# arduino.net
KiCad netlist of a schematic drawn in EAGLE
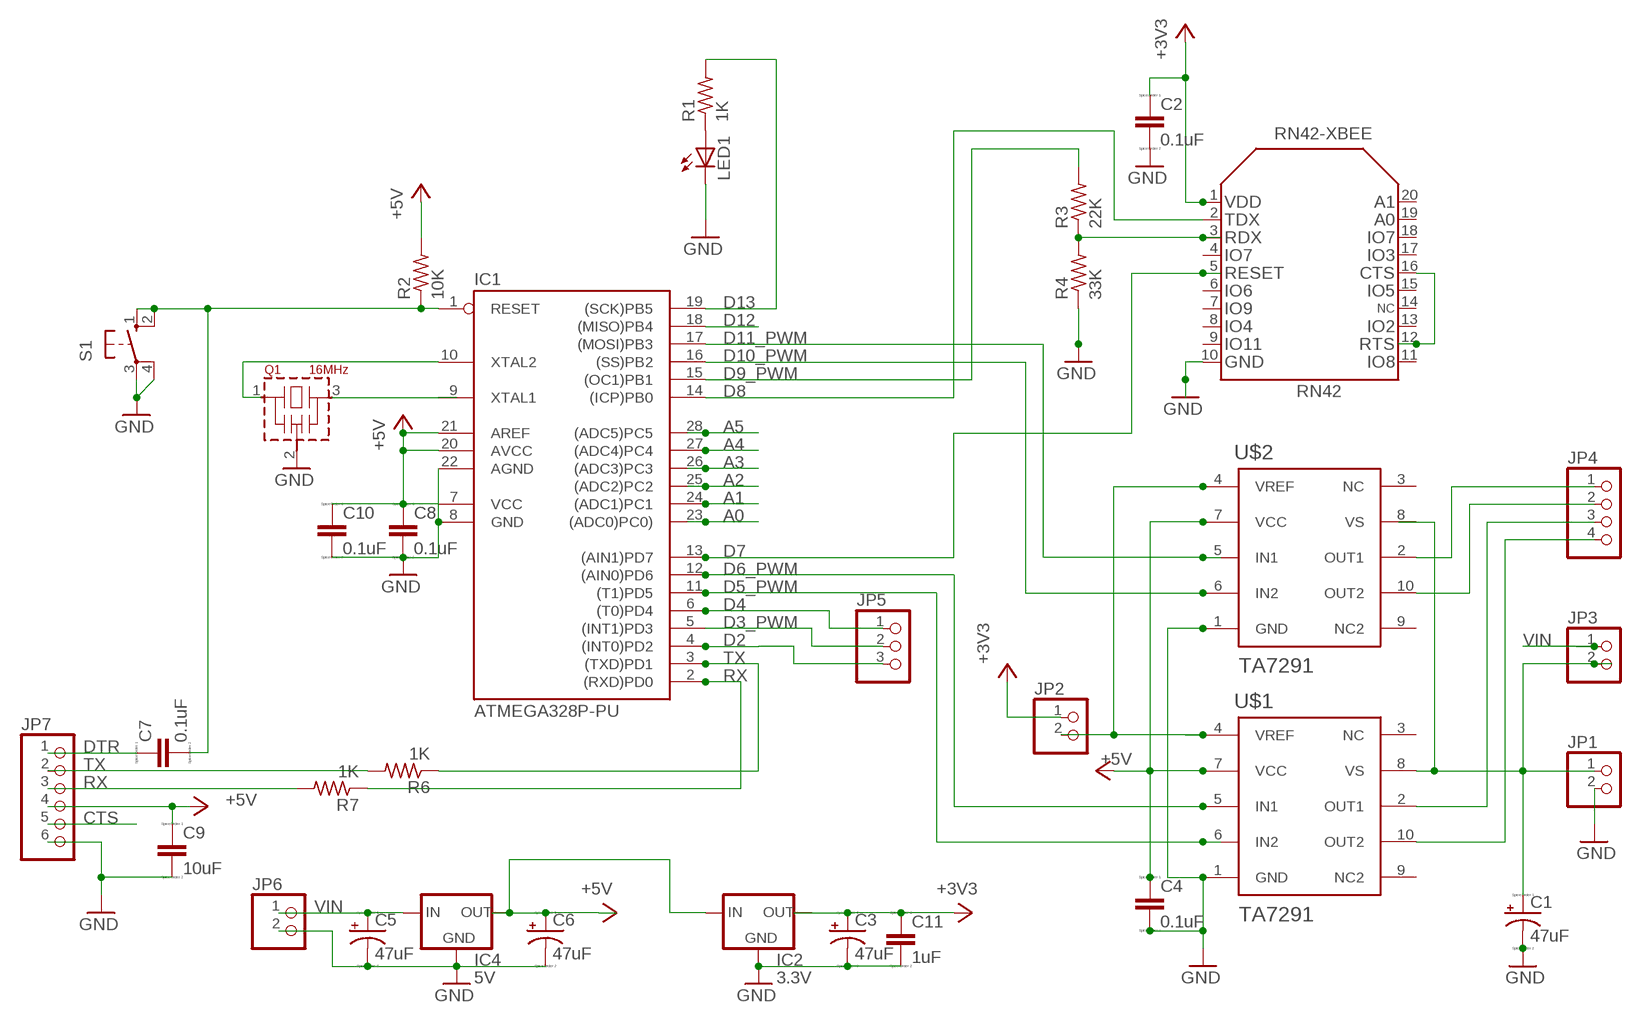
[diagram p0: schematic, sheet 1]

(export (version "E")
  (design (tool "Eeschema 10.0.6"))
  (components
    (comp (ref "C1")
      (value "47uF")
      (footprint "eagle-import:E2-5")
      (libsource (lib "eagle-import") (part "CPOL-USE2-5"))
    )
    (comp (ref "C2")
      (value "0.1uF")
      (footprint "eagle-import:C050-025X075")
      (libsource (lib "eagle-import") (part "C-EU050-025X075"))
    )
    (comp (ref "C3")
      (value "47uF")
      (footprint "eagle-import:E2-5")
      (libsource (lib "eagle-import") (part "CPOL-USE2-5"))
    )
    (comp (ref "C4")
      (value "0.1uF")
      (footprint "eagle-import:C050-025X075")
      (libsource (lib "eagle-import") (part "C-EU050-025X075"))
    )
    (comp (ref "C5")
      (value "47uF")
      (footprint "eagle-import:E2-5")
      (libsource (lib "eagle-import") (part "CPOL-USE2-5"))
    )
    (comp (ref "C6")
      (value "47uF")
      (footprint "eagle-import:E2-5")
      (libsource (lib "eagle-import") (part "CPOL-USE2-5"))
    )
    (comp (ref "C7")
      (value "0.1uF")
      (footprint "eagle-import:C050-025X075")
      (libsource (lib "eagle-import") (part "C-EU050-025X075"))
    )
    (comp (ref "C8")
      (value "0.1uF")
      (footprint "eagle-import:C050-025X075")
      (libsource (lib "eagle-import") (part "C-EU050-025X075"))
    )
    (comp (ref "C9")
      (value "10uF")
      (footprint "eagle-import:C050-025X075")
      (libsource (lib "eagle-import") (part "C-EU050-025X075"))
    )
    (comp (ref "C10")
      (value "0.1uF")
      (footprint "eagle-import:C050-025X075")
      (libsource (lib "eagle-import") (part "C-EU050-025X075"))
    )
    (comp (ref "C11")
      (value "1uF")
      (footprint "eagle-import:C050-025X075")
      (libsource (lib "eagle-import") (part "C-EU050-025X075"))
    )
    (comp (ref "IC1")
      (value "ATMEGA328P-PU")
      (footprint "eagle-import:DIL28-3")
      (libsource (lib "eagle-import") (part "ATMEGA328P-PU"))
    )
    (comp (ref "IC2")
      (value "3.3V")
      (footprint "eagle-import:78XXS")
      (libsource (lib "eagle-import") (part "78XXS"))
    )
    (comp (ref "IC4")
      (value "5V")
      (footprint "eagle-import:78XXS")
      (libsource (lib "eagle-import") (part "78XXS"))
    )
    (comp (ref "JP1")
      (value "PINHD-1X2")
      (footprint "eagle-import:1X02")
      (libsource (lib "eagle-import") (part "PINHD-1X2"))
    )
    (comp (ref "JP2")
      (value "PINHD-1X2")
      (footprint "eagle-import:1X02")
      (libsource (lib "eagle-import") (part "PINHD-1X2"))
    )
    (comp (ref "JP3")
      (value "PINHD-1X2")
      (footprint "eagle-import:1X02")
      (libsource (lib "eagle-import") (part "PINHD-1X2"))
    )
    (comp (ref "JP4")
      (value "PINHD-1X4")
      (footprint "eagle-import:1X04")
      (libsource (lib "eagle-import") (part "PINHD-1X4"))
    )
    (comp (ref "JP5")
      (value "PINHD-1X3")
      (footprint "eagle-import:1X03")
      (libsource (lib "eagle-import") (part "PINHD-1X3"))
    )
    (comp (ref "JP6")
      (value "PINHD-1X2")
      (footprint "eagle-import:1X02")
      (libsource (lib "eagle-import") (part "PINHD-1X2"))
    )
    (comp (ref "JP7")
      (value "PINHD-1X6")
      (footprint "eagle-import:1X06")
      (libsource (lib "eagle-import") (part "PINHD-1X6"))
    )
    (comp (ref "LED1")
      (value "LED3MM")
      (footprint "eagle-import:LED3MM")
      (libsource (lib "eagle-import") (part "LED3MM"))
    )
    (comp (ref "Q1")
      (value "16MHz")
      (footprint "eagle-import:CSTLS_G9")
      (libsource (lib "eagle-import") (part "murata-resonators_CSTLS_G"))
    )
    (comp (ref "R1")
      (value "1K")
      (footprint "eagle-import:0207_10")
      (libsource (lib "eagle-import") (part "R-US_0207/10"))
    )
    (comp (ref "R2")
      (value "10K")
      (footprint "eagle-import:0207_10")
      (libsource (lib "eagle-import") (part "R-US_0207/10"))
    )
    (comp (ref "R3")
      (value "22K")
      (footprint "eagle-import:0207_10")
      (libsource (lib "eagle-import") (part "R-US_0207/10"))
    )
    (comp (ref "R4")
      (value "33K")
      (footprint "eagle-import:0207_10")
      (libsource (lib "eagle-import") (part "R-US_0207/10"))
    )
    (comp (ref "R6")
      (value "1K")
      (footprint "eagle-import:0207_10")
      (libsource (lib "eagle-import") (part "R-US_0207/10"))
    )
    (comp (ref "R7")
      (value "1K")
      (footprint "eagle-import:0207_10")
      (libsource (lib "eagle-import") (part "R-US_0207/10"))
    )
    (comp (ref "S1")
      (value "10-XX")
      (footprint "eagle-import:B3F-10XX")
      (fields (field (name "MPN") "B3F-1000"))
      (libsource (lib "eagle-import") (part "10-XX"))
    )
    (comp (ref "U$1")
      (value "TA7291")
      (footprint "eagle-import:HSIP10")
      (libsource (lib "eagle-import") (part "TA7291"))
    )
    (comp (ref "U$2")
      (value "TA7291")
      (footprint "eagle-import:HSIP10")
      (libsource (lib "eagle-import") (part "TA7291"))
    )
    (comp (ref "U$3")
      (value "RN42-XBEE")
      (footprint "eagle-import:RN42-XBEE-PKG")
      (libsource (lib "eagle-import") (part "RN42-XBEE"))
    )
  )
  (nets
    (net (code "1") (name "+3V3") (class "Default")
      (node (ref "C11") (pin "1") (pinfunction "1_1") (pintype "passive"))
      (node (ref "C2") (pin "1") (pinfunction "1_1") (pintype "passive"))
      (node (ref "C3") (pin "+") (pinfunction "+_+") (pintype "passive"))
      (node (ref "IC2") (pin "OUT") (pinfunction "OUT_OUT") (pintype "passive"))
      (node (ref "JP2") (pin "1") (pinfunction "1_1") (pintype "passive"))
      (node (ref "U$3") (pin "1") (pinfunction "1_1") (pintype "passive"))
    )
    (net (code "2") (name "+5V") (class "Default")
      (node (ref "C10") (pin "1") (pinfunction "1_1") (pintype "passive"))
      (node (ref "C4") (pin "1") (pinfunction "1_1") (pintype "passive"))
      (node (ref "C6") (pin "+") (pinfunction "+_+") (pintype "passive"))
      (node (ref "C8") (pin "1") (pinfunction "1_1") (pintype "passive"))
      (node (ref "C9") (pin "1") (pinfunction "1_1") (pintype "passive"))
      (node (ref "IC1") (pin "20") (pinfunction "AVCC_20") (pintype "power_in"))
      (node (ref "IC1") (pin "21") (pinfunction "AREF_21") (pintype "passive"))
      (node (ref "IC1") (pin "7") (pinfunction "VCC_7") (pintype "power_in"))
      (node (ref "IC2") (pin "IN") (pinfunction "IN_IN") (pintype "input"))
      (node (ref "IC4") (pin "OUT") (pinfunction "OUT_OUT") (pintype "passive"))
      (node (ref "JP7") (pin "4") (pinfunction "4_4") (pintype "passive"))
      (node (ref "R2") (pin "2") (pinfunction "2_2") (pintype "passive"))
      (node (ref "U$1") (pin "7") (pinfunction "VCC_7") (pintype "bidirectional"))
      (node (ref "U$2") (pin "7") (pinfunction "VCC_7") (pintype "bidirectional"))
    )
    (net (code "3") (name "/A0") (class "Default")
      (node (ref "IC1") (pin "23") (pinfunction "(ADC0)PC0)_23") (pintype "bidirectional"))
    )
    (net (code "4") (name "/A1") (class "Default")
      (node (ref "IC1") (pin "24") (pinfunction "(ADC1)PC1_24") (pintype "bidirectional"))
    )
    (net (code "5") (name "/A2") (class "Default")
      (node (ref "IC1") (pin "25") (pinfunction "(ADC2)PC2_25") (pintype "bidirectional"))
    )
    (net (code "6") (name "/A3") (class "Default")
      (node (ref "IC1") (pin "26") (pinfunction "(ADC3)PC3_26") (pintype "bidirectional"))
    )
    (net (code "7") (name "/A4") (class "Default")
      (node (ref "IC1") (pin "27") (pinfunction "(ADC4)PC4_27") (pintype "bidirectional"))
    )
    (net (code "8") (name "/A5") (class "Default")
      (node (ref "IC1") (pin "28") (pinfunction "(ADC5)PC5_28") (pintype "bidirectional"))
    )
    (net (code "9") (name "/CTS") (class "Default")
      (node (ref "JP7") (pin "5") (pinfunction "5_5") (pintype "passive"))
    )
    (net (code "10") (name "/D2") (class "Default")
      (node (ref "IC1") (pin "4") (pinfunction "(INT0)PD2_4") (pintype "bidirectional"))
      (node (ref "JP5") (pin "3") (pinfunction "3_3") (pintype "passive"))
    )
    (net (code "11") (name "/D3_PWM") (class "Default")
      (node (ref "IC1") (pin "5") (pinfunction "(INT1)PD3_5") (pintype "bidirectional"))
      (node (ref "JP5") (pin "2") (pinfunction "2_2") (pintype "passive"))
    )
    (net (code "12") (name "/D4") (class "Default")
      (node (ref "IC1") (pin "6") (pinfunction "(T0)PD4_6") (pintype "bidirectional"))
      (node (ref "JP5") (pin "1") (pinfunction "1_1") (pintype "passive"))
    )
    (net (code "13") (name "/D5_PWM") (class "Default")
      (node (ref "IC1") (pin "11") (pinfunction "(T1)PD5_11") (pintype "bidirectional"))
      (node (ref "U$1") (pin "6") (pinfunction "IN2_6") (pintype "bidirectional"))
    )
    (net (code "14") (name "/D6_PWM") (class "Default")
      (node (ref "IC1") (pin "12") (pinfunction "(AIN0)PD6_12") (pintype "bidirectional"))
      (node (ref "U$1") (pin "5") (pinfunction "IN1_5") (pintype "bidirectional"))
    )
    (net (code "15") (name "/D7") (class "Default")
      (node (ref "IC1") (pin "13") (pinfunction "(AIN1)PD7_13") (pintype "bidirectional"))
      (node (ref "U$3") (pin "5") (pinfunction "5_5") (pintype "passive"))
    )
    (net (code "16") (name "/D8") (class "Default")
      (node (ref "IC1") (pin "14") (pinfunction "(ICP)PB0_14") (pintype "bidirectional"))
      (node (ref "U$3") (pin "2") (pinfunction "2_2") (pintype "passive"))
    )
    (net (code "17") (name "/D9_PWM") (class "Default")
      (node (ref "IC1") (pin "15") (pinfunction "(OC1)PB1_15") (pintype "bidirectional"))
      (node (ref "R3") (pin "2") (pinfunction "2_2") (pintype "passive"))
    )
    (net (code "18") (name "/D10_PWM") (class "Default")
      (node (ref "IC1") (pin "16") (pinfunction "(SS)PB2_16") (pintype "bidirectional"))
      (node (ref "U$2") (pin "6") (pinfunction "IN2_6") (pintype "bidirectional"))
    )
    (net (code "19") (name "/D11_PWM") (class "Default")
      (node (ref "IC1") (pin "17") (pinfunction "(MOSI)PB3_17") (pintype "bidirectional"))
      (node (ref "U$2") (pin "5") (pinfunction "IN1_5") (pintype "bidirectional"))
    )
    (net (code "20") (name "/D12") (class "Default")
      (node (ref "IC1") (pin "18") (pinfunction "(MISO)PB4_18") (pintype "bidirectional"))
    )
    (net (code "21") (name "/D13") (class "Default")
      (node (ref "IC1") (pin "19") (pinfunction "(SCK)PB5_19") (pintype "bidirectional"))
      (node (ref "R1") (pin "2") (pinfunction "2_2") (pintype "passive"))
    )
    (net (code "22") (name "/DTR") (class "Default")
      (node (ref "C7") (pin "1") (pinfunction "1_1") (pintype "passive"))
      (node (ref "JP7") (pin "1") (pinfunction "1_1") (pintype "passive"))
    )
    (net (code "23") (name "/RX") (class "Default")
      (node (ref "IC1") (pin "2") (pinfunction "(RXD)PD0_2") (pintype "bidirectional"))
      (node (ref "R7") (pin "1") (pinfunction "1_1") (pintype "passive"))
    )
    (net (code "24") (name "/TX") (class "Default")
      (node (ref "IC1") (pin "3") (pinfunction "(TXD)PD1_3") (pintype "bidirectional"))
      (node (ref "R6") (pin "1") (pinfunction "1_1") (pintype "passive"))
    )
    (net (code "25") (name "/VIN") (class "Default")
      (node (ref "C5") (pin "+") (pinfunction "+_+") (pintype "passive"))
      (node (ref "IC4") (pin "IN") (pinfunction "IN_IN") (pintype "input"))
      (node (ref "JP3") (pin "1") (pinfunction "1_1") (pintype "passive"))
      (node (ref "JP6") (pin "1") (pinfunction "1_1") (pintype "passive"))
    )
    (net (code "26") (name "GND") (class "Default")
      (node (ref "C1") (pin "-") (pinfunction "-_-") (pintype "passive"))
      (node (ref "C10") (pin "2") (pinfunction "2_2") (pintype "passive"))
      (node (ref "C11") (pin "2") (pinfunction "2_2") (pintype "passive"))
      (node (ref "C2") (pin "2") (pinfunction "2_2") (pintype "passive"))
      (node (ref "C3") (pin "-") (pinfunction "-_-") (pintype "passive"))
      (node (ref "C4") (pin "2") (pinfunction "2_2") (pintype "passive"))
      (node (ref "C5") (pin "-") (pinfunction "-_-") (pintype "passive"))
      (node (ref "C6") (pin "-") (pinfunction "-_-") (pintype "passive"))
      (node (ref "C8") (pin "2") (pinfunction "2_2") (pintype "passive"))
      (node (ref "C9") (pin "2") (pinfunction "2_2") (pintype "passive"))
      (node (ref "IC1") (pin "22") (pinfunction "AGND_22") (pintype "power_in"))
      (node (ref "IC1") (pin "8") (pinfunction "GND_8") (pintype "power_in"))
      (node (ref "IC2") (pin "GND") (pinfunction "GND_GND") (pintype "input"))
      (node (ref "IC4") (pin "GND") (pinfunction "GND_GND") (pintype "input"))
      (node (ref "JP1") (pin "2") (pinfunction "2_2") (pintype "passive"))
      (node (ref "JP6") (pin "2") (pinfunction "2_2") (pintype "passive"))
      (node (ref "JP7") (pin "6") (pinfunction "6_6") (pintype "passive"))
      (node (ref "LED1") (pin "K") (pinfunction "C_K") (pintype "passive"))
      (node (ref "Q1") (pin "2") (pinfunction "VSS_2") (pintype "power_in"))
      (node (ref "R4") (pin "1") (pinfunction "1_1") (pintype "passive"))
      (node (ref "S1") (pin "3") (pinfunction "P_3") (pintype "passive"))
      (node (ref "S1") (pin "4") (pinfunction "P1_4") (pintype "passive"))
      (node (ref "U$1") (pin "1") (pinfunction "GND_1") (pintype "bidirectional"))
      (node (ref "U$2") (pin "1") (pinfunction "GND_1") (pintype "bidirectional"))
      (node (ref "U$3") (pin "10") (pinfunction "10_10") (pintype "passive"))
    )
    (net (code "27") (name "Net-(IC1-RESET)") (class "Default")
      (node (ref "C7") (pin "2") (pinfunction "2_2") (pintype "passive"))
      (node (ref "IC1") (pin "1") (pinfunction "RESET_1") (pintype "input"))
      (node (ref "R2") (pin "1") (pinfunction "1_1") (pintype "passive"))
      (node (ref "S1") (pin "1") (pinfunction "S_1") (pintype "passive"))
      (node (ref "S1") (pin "2") (pinfunction "S1_2") (pintype "passive"))
    )
    (net (code "28") (name "Net-(IC1-XTAL1)") (class "Default")
      (node (ref "IC1") (pin "9") (pinfunction "XTAL1_9") (pintype "bidirectional"))
      (node (ref "Q1") (pin "3") (pinfunction "3_3") (pintype "input"))
    )
    (net (code "29") (name "Net-(IC1-XTAL2)") (class "Default")
      (node (ref "IC1") (pin "10") (pinfunction "XTAL2_10") (pintype "bidirectional"))
      (node (ref "Q1") (pin "1") (pinfunction "1_1") (pintype "output"))
    )
    (net (code "30") (name "Net-(JP7-Pad2)") (class "Default")
      (node (ref "JP7") (pin "2") (pinfunction "2_2") (pintype "passive"))
      (node (ref "R6") (pin "2") (pinfunction "2_2") (pintype "passive"))
    )
    (net (code "31") (name "Net-(JP7-Pad3)") (class "Default")
      (node (ref "JP7") (pin "3") (pinfunction "3_3") (pintype "passive"))
      (node (ref "R7") (pin "2") (pinfunction "2_2") (pintype "passive"))
    )
    (net (code "32") (name "Net-(LED1-PadA)") (class "Default")
      (node (ref "LED1") (pin "A") (pinfunction "A_A") (pintype "passive"))
      (node (ref "R1") (pin "1") (pinfunction "1_1") (pintype "passive"))
    )
    (net (code "33") (name "Net-(R3-Pad1)") (class "Default")
      (node (ref "R3") (pin "1") (pinfunction "1_1") (pintype "passive"))
      (node (ref "R4") (pin "2") (pinfunction "2_2") (pintype "passive"))
      (node (ref "U$3") (pin "3") (pinfunction "3_3") (pintype "passive"))
    )
    (net (code "34") (name "Net-(U$1-OUT1)") (class "Default")
      (node (ref "JP4") (pin "3") (pinfunction "3_3") (pintype "passive"))
      (node (ref "U$1") (pin "2") (pinfunction "OUT1_2") (pintype "bidirectional"))
    )
    (net (code "35") (name "Net-(U$1-OUT2)") (class "Default")
      (node (ref "JP4") (pin "4") (pinfunction "4_4") (pintype "passive"))
      (node (ref "U$1") (pin "10") (pinfunction "OUT2_10") (pintype "bidirectional"))
    )
    (net (code "36") (name "Net-(U$1-VREF)") (class "Default")
      (node (ref "JP2") (pin "2") (pinfunction "2_2") (pintype "passive"))
      (node (ref "U$1") (pin "4") (pinfunction "VREF_4") (pintype "bidirectional"))
      (node (ref "U$2") (pin "4") (pinfunction "VREF_4") (pintype "bidirectional"))
    )
    (net (code "37") (name "Net-(U$1-VS)") (class "Default")
      (node (ref "C1") (pin "+") (pinfunction "+_+") (pintype "passive"))
      (node (ref "JP1") (pin "1") (pinfunction "1_1") (pintype "passive"))
      (node (ref "JP3") (pin "2") (pinfunction "2_2") (pintype "passive"))
      (node (ref "U$1") (pin "8") (pinfunction "VS_8") (pintype "bidirectional"))
      (node (ref "U$2") (pin "8") (pinfunction "VS_8") (pintype "bidirectional"))
    )
    (net (code "38") (name "Net-(U$2-OUT1)") (class "Default")
      (node (ref "JP4") (pin "1") (pinfunction "1_1") (pintype "passive"))
      (node (ref "U$2") (pin "2") (pinfunction "OUT1_2") (pintype "bidirectional"))
    )
    (net (code "39") (name "Net-(U$2-OUT2)") (class "Default")
      (node (ref "JP4") (pin "2") (pinfunction "2_2") (pintype "passive"))
      (node (ref "U$2") (pin "10") (pinfunction "OUT2_10") (pintype "bidirectional"))
    )
    (net (code "40") (name "Net-(U$3-Pad12)") (class "Default")
      (node (ref "U$3") (pin "12") (pinfunction "12_12") (pintype "passive"))
      (node (ref "U$3") (pin "16") (pinfunction "16_16") (pintype "passive"))
    )
    (net (code "41") (name "unconnected-(U$1-NC-Pad3)") (class "Default")
      (node (ref "U$1") (pin "3") (pinfunction "NC_3") (pintype "bidirectional"))
    )
    (net (code "42") (name "unconnected-(U$1-NC2-Pad9)") (class "Default")
      (node (ref "U$1") (pin "9") (pinfunction "NC2_9") (pintype "bidirectional"))
    )
    (net (code "43") (name "unconnected-(U$2-NC-Pad3)") (class "Default")
      (node (ref "U$2") (pin "3") (pinfunction "NC_3") (pintype "bidirectional"))
    )
    (net (code "44") (name "unconnected-(U$2-NC2-Pad9)") (class "Default")
      (node (ref "U$2") (pin "9") (pinfunction "NC2_9") (pintype "bidirectional"))
    )
    (net (code "45") (name "unconnected-(U$3-Pad4)") (class "Default")
      (node (ref "U$3") (pin "4") (pinfunction "4_4") (pintype "passive"))
    )
    (net (code "46") (name "unconnected-(U$3-Pad6)") (class "Default")
      (node (ref "U$3") (pin "6") (pinfunction "6_6") (pintype "passive"))
    )
    (net (code "47") (name "unconnected-(U$3-Pad7)") (class "Default")
      (node (ref "U$3") (pin "7") (pinfunction "7_7") (pintype "passive"))
    )
    (net (code "48") (name "unconnected-(U$3-Pad8)") (class "Default")
      (node (ref "U$3") (pin "8") (pinfunction "8_8") (pintype "passive"))
    )
    (net (code "49") (name "unconnected-(U$3-Pad9)") (class "Default")
      (node (ref "U$3") (pin "9") (pinfunction "9_9") (pintype "passive"))
    )
    (net (code "50") (name "unconnected-(U$3-Pad11)") (class "Default")
      (node (ref "U$3") (pin "11") (pinfunction "11_11") (pintype "passive"))
    )
    (net (code "51") (name "unconnected-(U$3-Pad13)") (class "Default")
      (node (ref "U$3") (pin "13") (pinfunction "13_13") (pintype "passive"))
    )
    (net (code "52") (name "unconnected-(U$3-Pad14)") (class "Default")
      (node (ref "U$3") (pin "14") (pinfunction "14_14") (pintype "passive"))
    )
    (net (code "53") (name "unconnected-(U$3-Pad15)") (class "Default")
      (node (ref "U$3") (pin "15") (pinfunction "15_15") (pintype "passive"))
    )
    (net (code "54") (name "unconnected-(U$3-Pad17)") (class "Default")
      (node (ref "U$3") (pin "17") (pinfunction "17_17") (pintype "passive"))
    )
    (net (code "55") (name "unconnected-(U$3-Pad18)") (class "Default")
      (node (ref "U$3") (pin "18") (pinfunction "18_18") (pintype "passive"))
    )
    (net (code "56") (name "unconnected-(U$3-Pad19)") (class "Default")
      (node (ref "U$3") (pin "19") (pinfunction "19_19") (pintype "passive"))
    )
    (net (code "57") (name "unconnected-(U$3-Pad20)") (class "Default")
      (node (ref "U$3") (pin "20") (pinfunction "20_20") (pintype "passive"))
    )
  )
)
